# Prommer_nano_v2.net
KiCad netlist of a schematic drawn in EAGLE
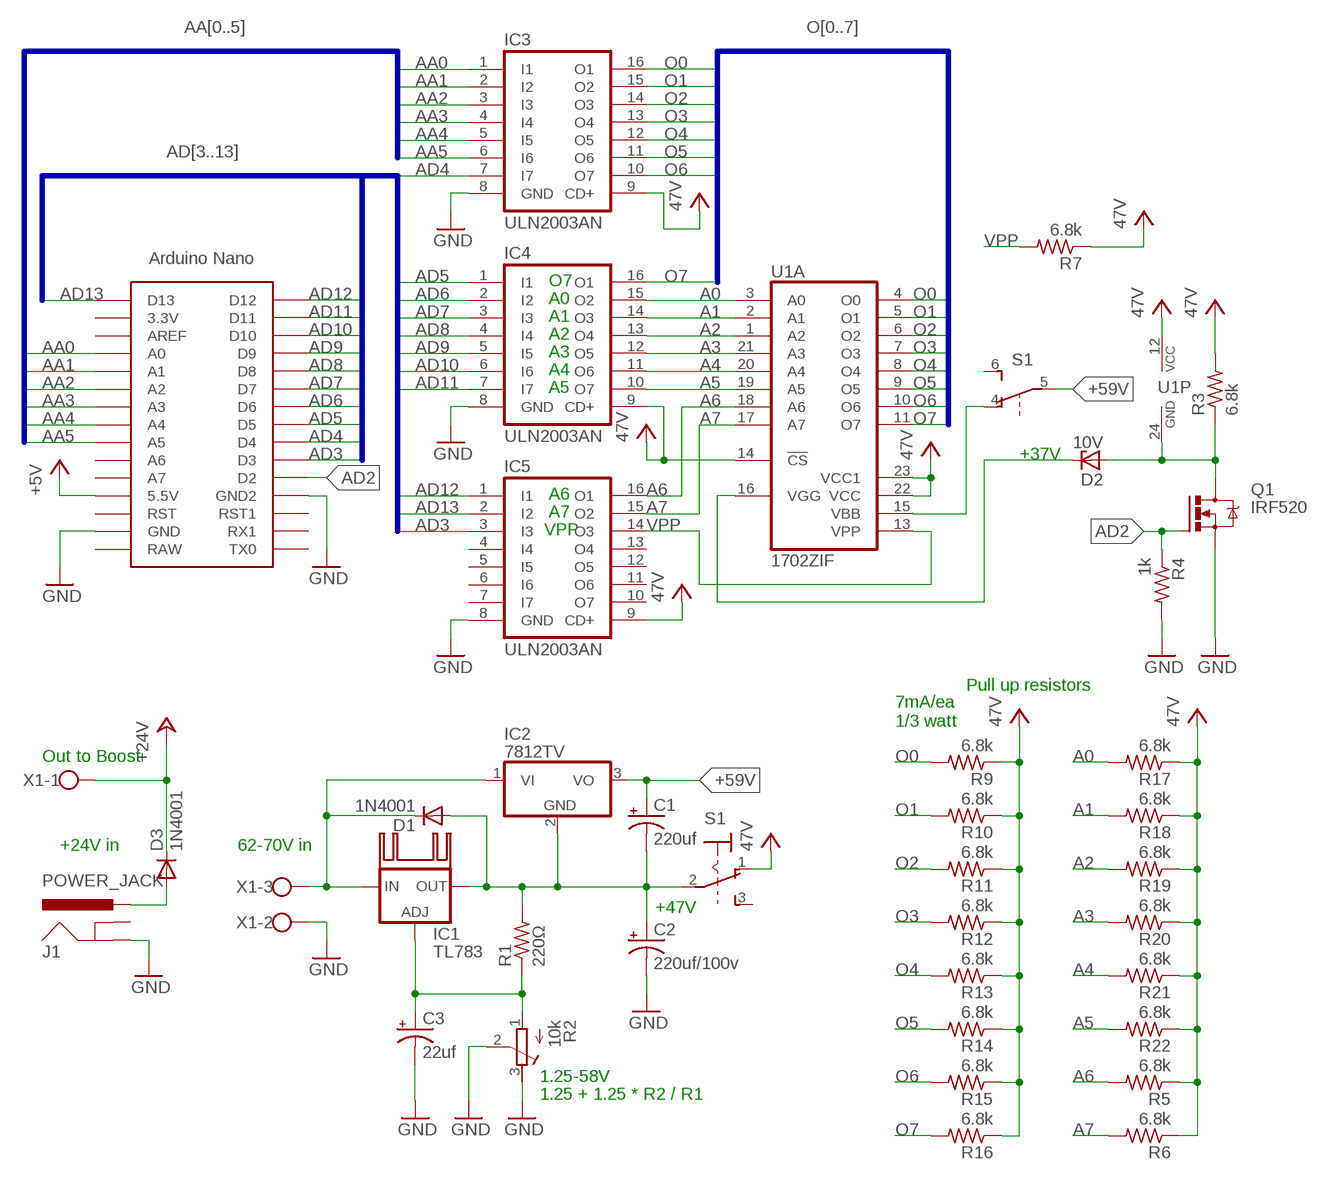
[diagram p0: schematic, sheet 1]

(export (version "E")
  (design (tool "Eeschema 10.0.6"))
  (components
    (comp (ref "C1")
      (value "220uf")
      (footprint "eagle-import:E5-10,5")
      (libsource (lib "eagle-import") (part "CPOL-USE5-10.5"))
    )
    (comp (ref "C2")
      (value "220uf/100v")
      (footprint "eagle-import:E5-13")
      (libsource (lib "eagle-import") (part "CPOL-USE5-13"))
    )
    (comp (ref "C3")
      (value "22uf")
      (footprint "eagle-import:E5-10,5")
      (libsource (lib "eagle-import") (part "CPOL-USE5-10.5"))
    )
    (comp (ref "D1")
      (value "1N4001")
      (footprint "eagle-import:D-7.5")
      (libsource (lib "eagle-import") (part "DIODE-D-7.5"))
    )
    (comp (ref "D2")
      (value "10V")
      (footprint "eagle-import:DO34Z7")
      (libsource (lib "eagle-import") (part "ZENER-DIODEDO34-7"))
    )
    (comp (ref "D3")
      (value "1N4001")
      (footprint "eagle-import:D-7.5")
      (libsource (lib "eagle-import") (part "DIODE-D-7.5"))
    )
    (comp (ref "IC1")
      (value "TL783")
      (footprint "eagle-import:317TS")
      (libsource (lib "eagle-import") (part "LM317TS"))
    )
    (comp (ref "IC2")
      (value "7812TV")
      (footprint "eagle-import:TO220V")
      (libsource (lib "eagle-import") (part "78TV12"))
    )
    (comp (ref "IC3")
      (value "ULN2003AN")
      (footprint "eagle-import:DIL16")
      (libsource (lib "eagle-import") (part "ULN2003AN"))
    )
    (comp (ref "IC4")
      (value "ULN2003AN")
      (footprint "eagle-import:DIL16")
      (libsource (lib "eagle-import") (part "ULN2003AN"))
    )
    (comp (ref "IC5")
      (value "ULN2003AN")
      (footprint "eagle-import:DIL16")
      (libsource (lib "eagle-import") (part "ULN2003AN"))
    )
    (comp (ref "J1")
      (value "POWER_JACK")
      (footprint "eagle-import:POWER_JACK_PTH")
      (libsource (lib "eagle-import") (part "POWER_JACK"))
    )
    (comp (ref "KK1")
      (value "SK95-2M3")
      (footprint "eagle-import:SK95-2M3")
      (libsource (lib "eagle-import") (part "SK95-2M3"))
    )
    (comp (ref "Q1")
      (value "IRF520")
      (footprint "eagle-import:TO220BV")
      (libsource (lib "eagle-import") (part "IRF520"))
    )
    (comp (ref "R1")
      (value "220Ω")
      (footprint "eagle-import:0207_10")
      (libsource (lib "eagle-import") (part "R-US_0207/10"))
    )
    (comp (ref "R2")
      (value "10k")
      (footprint "eagle-import:RTRIM64W")
      (libsource (lib "eagle-import") (part "R-TRIMM64W"))
    )
    (comp (ref "R3")
      (value "6.8k")
      (footprint "eagle-import:0207_10")
      (libsource (lib "eagle-import") (part "R-US_0207/10"))
    )
    (comp (ref "R4")
      (value "1k")
      (footprint "eagle-import:0207_10")
      (libsource (lib "eagle-import") (part "R-US_0207/10"))
    )
    (comp (ref "R5")
      (value "6.8k")
      (footprint "eagle-import:0207_10")
      (libsource (lib "eagle-import") (part "R-US_0207/10"))
    )
    (comp (ref "R6")
      (value "6.8k")
      (footprint "eagle-import:0207_10")
      (libsource (lib "eagle-import") (part "R-US_0207/10"))
    )
    (comp (ref "R7")
      (value "6.8k")
      (footprint "eagle-import:0207_10")
      (libsource (lib "eagle-import") (part "R-US_0207/10"))
    )
    (comp (ref "R9")
      (value "6.8k")
      (footprint "eagle-import:0207_10")
      (libsource (lib "eagle-import") (part "R-US_0207/10"))
    )
    (comp (ref "R10")
      (value "6.8k")
      (footprint "eagle-import:0207_10")
      (libsource (lib "eagle-import") (part "R-US_0207/10"))
    )
    (comp (ref "R11")
      (value "6.8k")
      (footprint "eagle-import:0207_10")
      (libsource (lib "eagle-import") (part "R-US_0207/10"))
    )
    (comp (ref "R12")
      (value "6.8k")
      (footprint "eagle-import:0207_10")
      (libsource (lib "eagle-import") (part "R-US_0207/10"))
    )
    (comp (ref "R13")
      (value "6.8k")
      (footprint "eagle-import:0207_10")
      (libsource (lib "eagle-import") (part "R-US_0207/10"))
    )
    (comp (ref "R14")
      (value "6.8k")
      (footprint "eagle-import:0207_10")
      (libsource (lib "eagle-import") (part "R-US_0207/10"))
    )
    (comp (ref "R15")
      (value "6.8k")
      (footprint "eagle-import:0207_10")
      (libsource (lib "eagle-import") (part "R-US_0207/10"))
    )
    (comp (ref "R16")
      (value "6.8k")
      (footprint "eagle-import:0207_10")
      (libsource (lib "eagle-import") (part "R-US_0207/10"))
    )
    (comp (ref "R17")
      (value "6.8k")
      (footprint "eagle-import:0207_10")
      (libsource (lib "eagle-import") (part "R-US_0207/10"))
    )
    (comp (ref "R18")
      (value "6.8k")
      (footprint "eagle-import:0207_10")
      (libsource (lib "eagle-import") (part "R-US_0207/10"))
    )
    (comp (ref "R19")
      (value "6.8k")
      (footprint "eagle-import:0207_10")
      (libsource (lib "eagle-import") (part "R-US_0207/10"))
    )
    (comp (ref "R20")
      (value "6.8k")
      (footprint "eagle-import:0207_10")
      (libsource (lib "eagle-import") (part "R-US_0207/10"))
    )
    (comp (ref "R21")
      (value "6.8k")
      (footprint "eagle-import:0207_10")
      (libsource (lib "eagle-import") (part "R-US_0207/10"))
    )
    (comp (ref "R22")
      (value "6.8k")
      (footprint "eagle-import:0207_10")
      (libsource (lib "eagle-import") (part "R-US_0207/10"))
    )
    (comp (ref "S1")
      (value "320-938")
      (footprint "eagle-import:320-938")
      (libsource (lib "eagle-import") (part "320-938"))
    )
    (comp (ref "U$1")
      (value "NANO")
      (footprint "eagle-import:NANO")
      (libsource (lib "eagle-import") (part "NANO"))
    )
    (comp (ref "U1")
      (value "1702ZIF")
      (footprint "eagle-import:ZIF24")
      (libsource (lib "eagle-import") (part "1702ZIF"))
    )
    (comp (ref "X1")
      (value "W237-103")
      (footprint "eagle-import:W237-103")
      (fields (field (name "MPN") "237-103"))
      (libsource (lib "eagle-import") (part "W237-103"))
    )
  )
  (nets
    (net (code "1") (name "+5V") (class "Default")
      (node (ref "U$1") (pin "5V") (pinfunction "5.5V_5V") (pintype "bidirectional"))
    )
    (net (code "2") (name "+24V") (class "Default")
      (node (ref "D3") (pin "C") (pinfunction "C_C") (pintype "passive"))
      (node (ref "X1") (pin "1") (pinfunction "KL_1") (pintype "passive"))
    )
    (net (code "3") (name "+59V") (class "Default")
      (node (ref "C1") (pin "+") (pinfunction "+_+") (pintype "passive"))
      (node (ref "IC2") (pin "3") (pinfunction "VO_3") (pintype "passive"))
      (node (ref "S1") (pin "5") (pinfunction "P_5") (pintype "passive"))
    )
    (net (code "4") (name "/A0") (class "Default")
      (node (ref "IC4") (pin "15") (pinfunction "O2_15") (pintype "open_collector"))
      (node (ref "R17") (pin "2") (pinfunction "2_2") (pintype "passive"))
      (node (ref "U1") (pin "3") (pinfunction "A0_3") (pintype "input"))
    )
    (net (code "5") (name "/A1") (class "Default")
      (node (ref "IC4") (pin "14") (pinfunction "O3_14") (pintype "open_collector"))
      (node (ref "R18") (pin "2") (pinfunction "2_2") (pintype "passive"))
      (node (ref "U1") (pin "2") (pinfunction "A1_2") (pintype "input"))
    )
    (net (code "6") (name "/A2") (class "Default")
      (node (ref "IC4") (pin "13") (pinfunction "O4_13") (pintype "open_collector"))
      (node (ref "R19") (pin "2") (pinfunction "2_2") (pintype "passive"))
      (node (ref "U1") (pin "1") (pinfunction "A2_1") (pintype "input"))
    )
    (net (code "7") (name "/A3") (class "Default")
      (node (ref "IC4") (pin "12") (pinfunction "O5_12") (pintype "open_collector"))
      (node (ref "R20") (pin "2") (pinfunction "2_2") (pintype "passive"))
      (node (ref "U1") (pin "21") (pinfunction "A3_21") (pintype "input"))
    )
    (net (code "8") (name "/A4") (class "Default")
      (node (ref "IC4") (pin "11") (pinfunction "O6_11") (pintype "open_collector"))
      (node (ref "R21") (pin "2") (pinfunction "2_2") (pintype "passive"))
      (node (ref "U1") (pin "20") (pinfunction "A4_20") (pintype "input"))
    )
    (net (code "9") (name "/A5") (class "Default")
      (node (ref "IC4") (pin "10") (pinfunction "O7_10") (pintype "open_collector"))
      (node (ref "R22") (pin "2") (pinfunction "2_2") (pintype "passive"))
      (node (ref "U1") (pin "19") (pinfunction "A5_19") (pintype "input"))
    )
    (net (code "10") (name "/A6") (class "Default")
      (node (ref "IC5") (pin "16") (pinfunction "O1_16") (pintype "open_collector"))
      (node (ref "R5") (pin "2") (pinfunction "2_2") (pintype "passive"))
      (node (ref "U1") (pin "18") (pinfunction "A6_18") (pintype "input"))
    )
    (net (code "11") (name "/A7") (class "Default")
      (node (ref "IC5") (pin "15") (pinfunction "O2_15") (pintype "open_collector"))
      (node (ref "R6") (pin "2") (pinfunction "2_2") (pintype "passive"))
      (node (ref "U1") (pin "17") (pinfunction "A7_17") (pintype "input"))
    )
    (net (code "12") (name "/AA0") (class "Default")
      (node (ref "IC3") (pin "1") (pinfunction "I1_1") (pintype "input"))
      (node (ref "U$1") (pin "A0") (pinfunction "A0_A0") (pintype "bidirectional"))
    )
    (net (code "13") (name "/AA1") (class "Default")
      (node (ref "IC3") (pin "2") (pinfunction "I2_2") (pintype "input"))
      (node (ref "U$1") (pin "A1") (pinfunction "A1_A1") (pintype "bidirectional"))
    )
    (net (code "14") (name "/AA2") (class "Default")
      (node (ref "IC3") (pin "3") (pinfunction "I3_3") (pintype "input"))
      (node (ref "U$1") (pin "A2") (pinfunction "A2_A2") (pintype "bidirectional"))
    )
    (net (code "15") (name "/AA3") (class "Default")
      (node (ref "IC3") (pin "4") (pinfunction "I4_4") (pintype "input"))
      (node (ref "U$1") (pin "A3") (pinfunction "A3_A3") (pintype "bidirectional"))
    )
    (net (code "16") (name "/AA4") (class "Default")
      (node (ref "IC3") (pin "5") (pinfunction "I5_5") (pintype "input"))
      (node (ref "U$1") (pin "A4") (pinfunction "A4_A4") (pintype "bidirectional"))
    )
    (net (code "17") (name "/AA5") (class "Default")
      (node (ref "IC3") (pin "6") (pinfunction "I6_6") (pintype "input"))
      (node (ref "U$1") (pin "A5") (pinfunction "A5_A5") (pintype "bidirectional"))
    )
    (net (code "19") (name "/AD3") (class "Default")
      (node (ref "IC5") (pin "3") (pinfunction "I3_3") (pintype "input"))
      (node (ref "U$1") (pin "D3") (pinfunction "D3_D3") (pintype "bidirectional"))
    )
    (net (code "20") (name "/AD4") (class "Default")
      (node (ref "IC3") (pin "7") (pinfunction "I7_7") (pintype "input"))
      (node (ref "U$1") (pin "D4") (pinfunction "D4_D4") (pintype "bidirectional"))
    )
    (net (code "21") (name "/AD5") (class "Default")
      (node (ref "IC4") (pin "1") (pinfunction "I1_1") (pintype "input"))
      (node (ref "U$1") (pin "D5") (pinfunction "D5_D5") (pintype "bidirectional"))
    )
    (net (code "22") (name "/AD6") (class "Default")
      (node (ref "IC4") (pin "2") (pinfunction "I2_2") (pintype "input"))
      (node (ref "U$1") (pin "D6") (pinfunction "D6_D6") (pintype "bidirectional"))
    )
    (net (code "23") (name "/AD7") (class "Default")
      (node (ref "IC4") (pin "3") (pinfunction "I3_3") (pintype "input"))
      (node (ref "U$1") (pin "D7") (pinfunction "D7_D7") (pintype "bidirectional"))
    )
    (net (code "24") (name "/AD8") (class "Default")
      (node (ref "IC4") (pin "4") (pinfunction "I4_4") (pintype "input"))
      (node (ref "U$1") (pin "D8") (pinfunction "D8_D8") (pintype "bidirectional"))
    )
    (net (code "25") (name "/AD9") (class "Default")
      (node (ref "IC4") (pin "5") (pinfunction "I5_5") (pintype "input"))
      (node (ref "U$1") (pin "D9") (pinfunction "D9_D9") (pintype "bidirectional"))
    )
    (net (code "26") (name "/AD10") (class "Default")
      (node (ref "IC4") (pin "6") (pinfunction "I6_6") (pintype "input"))
      (node (ref "U$1") (pin "D10") (pinfunction "D10_D10") (pintype "bidirectional"))
    )
    (net (code "27") (name "/AD11") (class "Default")
      (node (ref "IC4") (pin "7") (pinfunction "I7_7") (pintype "input"))
      (node (ref "U$1") (pin "D11") (pinfunction "D11_D11") (pintype "bidirectional"))
    )
    (net (code "28") (name "/AD12") (class "Default")
      (node (ref "IC5") (pin "1") (pinfunction "I1_1") (pintype "input"))
      (node (ref "U$1") (pin "D12") (pinfunction "D12_D12") (pintype "bidirectional"))
    )
    (net (code "29") (name "/AD13") (class "Default")
      (node (ref "IC5") (pin "2") (pinfunction "I2_2") (pintype "input"))
      (node (ref "U$1") (pin "D13") (pinfunction "D13_D13") (pintype "bidirectional"))
    )
    (net (code "31") (name "/O0") (class "Default")
      (node (ref "IC3") (pin "16") (pinfunction "O1_16") (pintype "open_collector"))
      (node (ref "R9") (pin "2") (pinfunction "2_2") (pintype "passive"))
      (node (ref "U1") (pin "4") (pinfunction "O0_4") (pintype "tri_state"))
    )
    (net (code "32") (name "/O1") (class "Default")
      (node (ref "IC3") (pin "15") (pinfunction "O2_15") (pintype "open_collector"))
      (node (ref "R10") (pin "2") (pinfunction "2_2") (pintype "passive"))
      (node (ref "U1") (pin "5") (pinfunction "O1_5") (pintype "tri_state"))
    )
    (net (code "33") (name "/O2") (class "Default")
      (node (ref "IC3") (pin "14") (pinfunction "O3_14") (pintype "open_collector"))
      (node (ref "R11") (pin "2") (pinfunction "2_2") (pintype "passive"))
      (node (ref "U1") (pin "6") (pinfunction "O2_6") (pintype "tri_state"))
    )
    (net (code "34") (name "/O3") (class "Default")
      (node (ref "IC3") (pin "13") (pinfunction "O4_13") (pintype "open_collector"))
      (node (ref "R12") (pin "2") (pinfunction "2_2") (pintype "passive"))
      (node (ref "U1") (pin "7") (pinfunction "O3_7") (pintype "tri_state"))
    )
    (net (code "35") (name "/O4") (class "Default")
      (node (ref "IC3") (pin "12") (pinfunction "O5_12") (pintype "open_collector"))
      (node (ref "R13") (pin "2") (pinfunction "2_2") (pintype "passive"))
      (node (ref "U1") (pin "8") (pinfunction "O4_8") (pintype "tri_state"))
    )
    (net (code "36") (name "/O5") (class "Default")
      (node (ref "IC3") (pin "11") (pinfunction "O6_11") (pintype "open_collector"))
      (node (ref "R14") (pin "2") (pinfunction "2_2") (pintype "passive"))
      (node (ref "U1") (pin "9") (pinfunction "O5_9") (pintype "tri_state"))
    )
    (net (code "37") (name "/O6") (class "Default")
      (node (ref "IC3") (pin "10") (pinfunction "O7_10") (pintype "open_collector"))
      (node (ref "R15") (pin "2") (pinfunction "2_2") (pintype "passive"))
      (node (ref "U1") (pin "10") (pinfunction "O6_10") (pintype "tri_state"))
    )
    (net (code "38") (name "/O7") (class "Default")
      (node (ref "IC4") (pin "16") (pinfunction "O1_16") (pintype "open_collector"))
      (node (ref "R16") (pin "2") (pinfunction "2_2") (pintype "passive"))
      (node (ref "U1") (pin "11") (pinfunction "O7_11") (pintype "tri_state"))
    )
    (net (code "40") (name "/VPP") (class "Default")
      (node (ref "IC5") (pin "14") (pinfunction "O3_14") (pintype "open_collector"))
      (node (ref "R7") (pin "2") (pinfunction "2_2") (pintype "passive"))
      (node (ref "U1") (pin "13") (pinfunction "VPP_13") (pintype "input"))
    )
    (net (code "41") (name "47V") (class "Default")
      (node (ref "IC3") (pin "9") (pinfunction "CD+_9") (pintype "passive"))
      (node (ref "IC4") (pin "9") (pinfunction "CD+_9") (pintype "passive"))
      (node (ref "IC5") (pin "9") (pinfunction "CD+_9") (pintype "passive"))
      (node (ref "R10") (pin "1") (pinfunction "1_1") (pintype "passive"))
      (node (ref "R11") (pin "1") (pinfunction "1_1") (pintype "passive"))
      (node (ref "R12") (pin "1") (pinfunction "1_1") (pintype "passive"))
      (node (ref "R13") (pin "1") (pinfunction "1_1") (pintype "passive"))
      (node (ref "R14") (pin "1") (pinfunction "1_1") (pintype "passive"))
      (node (ref "R15") (pin "1") (pinfunction "1_1") (pintype "passive"))
      (node (ref "R16") (pin "1") (pinfunction "1_1") (pintype "passive"))
      (node (ref "R17") (pin "1") (pinfunction "1_1") (pintype "passive"))
      (node (ref "R18") (pin "1") (pinfunction "1_1") (pintype "passive"))
      (node (ref "R19") (pin "1") (pinfunction "1_1") (pintype "passive"))
      (node (ref "R20") (pin "1") (pinfunction "1_1") (pintype "passive"))
      (node (ref "R21") (pin "1") (pinfunction "1_1") (pintype "passive"))
      (node (ref "R22") (pin "1") (pinfunction "1_1") (pintype "passive"))
      (node (ref "R3") (pin "2") (pinfunction "2_2") (pintype "passive"))
      (node (ref "R5") (pin "1") (pinfunction "1_1") (pintype "passive"))
      (node (ref "R6") (pin "1") (pinfunction "1_1") (pintype "passive"))
      (node (ref "R7") (pin "1") (pinfunction "1_1") (pintype "passive"))
      (node (ref "R9") (pin "1") (pinfunction "1_1") (pintype "passive"))
      (node (ref "S1") (pin "1") (pinfunction "O_1") (pintype "passive"))
      (node (ref "U1") (pin "12") (pinfunction "VCC_12") (pintype "power_in"))
      (node (ref "U1") (pin "14") (pinfunction "~{CS}_14") (pintype "input"))
      (node (ref "U1") (pin "22") (pinfunction "VCC_22") (pintype "input"))
      (node (ref "U1") (pin "23") (pinfunction "VCC1_23") (pintype "input"))
    )
    (net (code "42") (name "AD2") (class "Default")
      (node (ref "Q1") (pin "G") (pinfunction "G_G") (pintype "passive"))
      (node (ref "R4") (pin "1") (pinfunction "1_1") (pintype "passive"))
      (node (ref "U$1") (pin "D2") (pinfunction "D2_D2") (pintype "bidirectional"))
    )
    (net (code "43") (name "GND") (class "Default")
      (node (ref "C2") (pin "-") (pinfunction "-_-") (pintype "passive"))
      (node (ref "C3") (pin "-") (pinfunction "-_-") (pintype "passive"))
      (node (ref "IC3") (pin "8") (pinfunction "GND_8") (pintype "power_in"))
      (node (ref "IC4") (pin "8") (pinfunction "GND_8") (pintype "power_in"))
      (node (ref "IC5") (pin "8") (pinfunction "GND_8") (pintype "power_in"))
      (node (ref "J1") (pin "GND") (pinfunction "GND_GND") (pintype "bidirectional"))
      (node (ref "Q1") (pin "S") (pinfunction "S_S") (pintype "passive"))
      (node (ref "R2") (pin "2") (pinfunction "S_2") (pintype "passive"))
      (node (ref "R2") (pin "3") (pinfunction "E_3") (pintype "passive"))
      (node (ref "R4") (pin "2") (pinfunction "2_2") (pintype "passive"))
      (node (ref "U$1") (pin "GND") (pinfunction "GND_GND") (pintype "bidirectional"))
      (node (ref "U$1") (pin "GND1") (pinfunction "GND2_GND1") (pintype "bidirectional"))
      (node (ref "X1") (pin "2") (pinfunction "KL_2") (pintype "passive"))
    )
    (net (code "44") (name "Net-(D3-PadA)") (class "Default")
      (node (ref "D3") (pin "A") (pinfunction "A_A") (pintype "passive"))
      (node (ref "J1") (pin "PWR") (pinfunction "PWR_PWR") (pintype "bidirectional"))
    )
    (net (code "45") (name "Net-(IC1-ADJ)") (class "Default")
      (node (ref "C3") (pin "+") (pinfunction "+_+") (pintype "passive"))
      (node (ref "IC1") (pin "1") (pinfunction "ADJ_1") (pintype "input"))
      (node (ref "R1") (pin "1") (pinfunction "1_1") (pintype "passive"))
      (node (ref "R2") (pin "1") (pinfunction "A_1") (pintype "passive"))
    )
    (net (code "46") (name "Net-(IC1-IN)") (class "Default")
      (node (ref "D1") (pin "C") (pinfunction "C_C") (pintype "passive"))
      (node (ref "IC1") (pin "3") (pinfunction "IN_3") (pintype "input"))
      (node (ref "IC2") (pin "1") (pinfunction "VI_1") (pintype "input"))
      (node (ref "X1") (pin "3") (pinfunction "KL_3") (pintype "passive"))
    )
    (net (code "47") (name "Net-(IC1-OUT)") (class "Default")
      (node (ref "C1") (pin "-") (pinfunction "-_-") (pintype "passive"))
      (node (ref "C2") (pin "+") (pinfunction "+_+") (pintype "passive"))
      (node (ref "D1") (pin "A") (pinfunction "A_A") (pintype "passive"))
      (node (ref "IC1") (pin "2") (pinfunction "OUT_2") (pintype "passive"))
      (node (ref "IC2") (pin "2") (pinfunction "GND_2") (pintype "passive"))
      (node (ref "R1") (pin "2") (pinfunction "2_2") (pintype "passive"))
      (node (ref "S1") (pin "2") (pinfunction "P_2") (pintype "passive"))
    )
    (net (code "48") (name "Net-(S1B-O)") (class "Default")
      (node (ref "S1") (pin "4") (pinfunction "O_4") (pintype "passive"))
      (node (ref "U1") (pin "15") (pinfunction "VBB_15") (pintype "input"))
    )
    (net (code "49") (name "Net-(U1A-VGG)") (class "Default")
      (node (ref "D2") (pin "C") (pinfunction "C_C") (pintype "passive"))
      (node (ref "U1") (pin "16") (pinfunction "VGG_16") (pintype "input"))
    )
    (net (code "50") (name "Net-(U1B-GND)") (class "Default")
      (node (ref "D2") (pin "A") (pinfunction "A_A") (pintype "passive"))
      (node (ref "Q1") (pin "D") (pinfunction "D_D") (pintype "passive"))
      (node (ref "R3") (pin "1") (pinfunction "1_1") (pintype "passive"))
      (node (ref "U1") (pin "24") (pinfunction "GND_24") (pintype "power_in"))
    )
    (net (code "51") (name "unconnected-(IC5-I4-Pad4)") (class "Default")
      (node (ref "IC5") (pin "4") (pinfunction "I4_4") (pintype "input"))
    )
    (net (code "52") (name "unconnected-(IC5-I5-Pad5)") (class "Default")
      (node (ref "IC5") (pin "5") (pinfunction "I5_5") (pintype "input"))
    )
    (net (code "53") (name "unconnected-(IC5-I6-Pad6)") (class "Default")
      (node (ref "IC5") (pin "6") (pinfunction "I6_6") (pintype "input"))
    )
    (net (code "54") (name "unconnected-(IC5-I7-Pad7)") (class "Default")
      (node (ref "IC5") (pin "7") (pinfunction "I7_7") (pintype "input"))
    )
    (net (code "55") (name "unconnected-(IC5-O4-Pad13)") (class "Default")
      (node (ref "IC5") (pin "13") (pinfunction "O4_13") (pintype "open_collector"))
    )
    (net (code "56") (name "unconnected-(IC5-O5-Pad12)") (class "Default")
      (node (ref "IC5") (pin "12") (pinfunction "O5_12") (pintype "open_collector"))
    )
    (net (code "57") (name "unconnected-(IC5-O6-Pad11)") (class "Default")
      (node (ref "IC5") (pin "11") (pinfunction "O6_11") (pintype "open_collector"))
    )
    (net (code "58") (name "unconnected-(IC5-O7-Pad10)") (class "Default")
      (node (ref "IC5") (pin "10") (pinfunction "O7_10") (pintype "open_collector"))
    )
    (net (code "59") (name "unconnected-(J1-PadGNDBREAK)") (class "Default")
      (node (ref "J1") (pin "GNDBREAK") (pinfunction "GNDBREAK_GNDBREAK") (pintype "bidirectional"))
    )
    (net (code "60") (name "unconnected-(S1A-S-Pad3)") (class "Default")
      (node (ref "S1") (pin "3") (pinfunction "S_3") (pintype "passive"))
    )
    (net (code "61") (name "unconnected-(S1B-S-Pad6)") (class "Default")
      (node (ref "S1") (pin "6") (pinfunction "S_6") (pintype "passive"))
    )
    (net (code "62") (name "unconnected-(U$1-Pad3.3V)") (class "Default")
      (node (ref "U$1") (pin "3.3V") (pinfunction "3.3V_3.3V") (pintype "bidirectional"))
    )
    (net (code "63") (name "unconnected-(U$1-PadA6)") (class "Default")
      (node (ref "U$1") (pin "A6") (pinfunction "A6_A6") (pintype "bidirectional"))
    )
    (net (code "64") (name "unconnected-(U$1-PadA7)") (class "Default")
      (node (ref "U$1") (pin "A7") (pinfunction "A7_A7") (pintype "bidirectional"))
    )
    (net (code "65") (name "unconnected-(U$1-PadAREF)") (class "Default")
      (node (ref "U$1") (pin "AREF") (pinfunction "AREF_AREF") (pintype "bidirectional"))
    )
    (net (code "66") (name "unconnected-(U$1-PadRAW)") (class "Default")
      (node (ref "U$1") (pin "RAW") (pinfunction "RAW_RAW") (pintype "bidirectional"))
    )
    (net (code "67") (name "unconnected-(U$1-PadRST)") (class "Default")
      (node (ref "U$1") (pin "RST") (pinfunction "RST_RST") (pintype "bidirectional"))
    )
    (net (code "68") (name "unconnected-(U$1-PadRST1)") (class "Default")
      (node (ref "U$1") (pin "RST1") (pinfunction "RST1_RST1") (pintype "bidirectional"))
    )
    (net (code "69") (name "unconnected-(U$1-PadRX1)") (class "Default")
      (node (ref "U$1") (pin "RX1") (pinfunction "RX1_RX1") (pintype "bidirectional"))
    )
    (net (code "70") (name "unconnected-(U$1-PadTX0)") (class "Default")
      (node (ref "U$1") (pin "TX0") (pinfunction "TX0_TX0") (pintype "bidirectional"))
    )
  )
)
